# DPSD_NANO_2020-07-29_17-39-39.net
KiCad netlist of a schematic drawn in EasyEDA
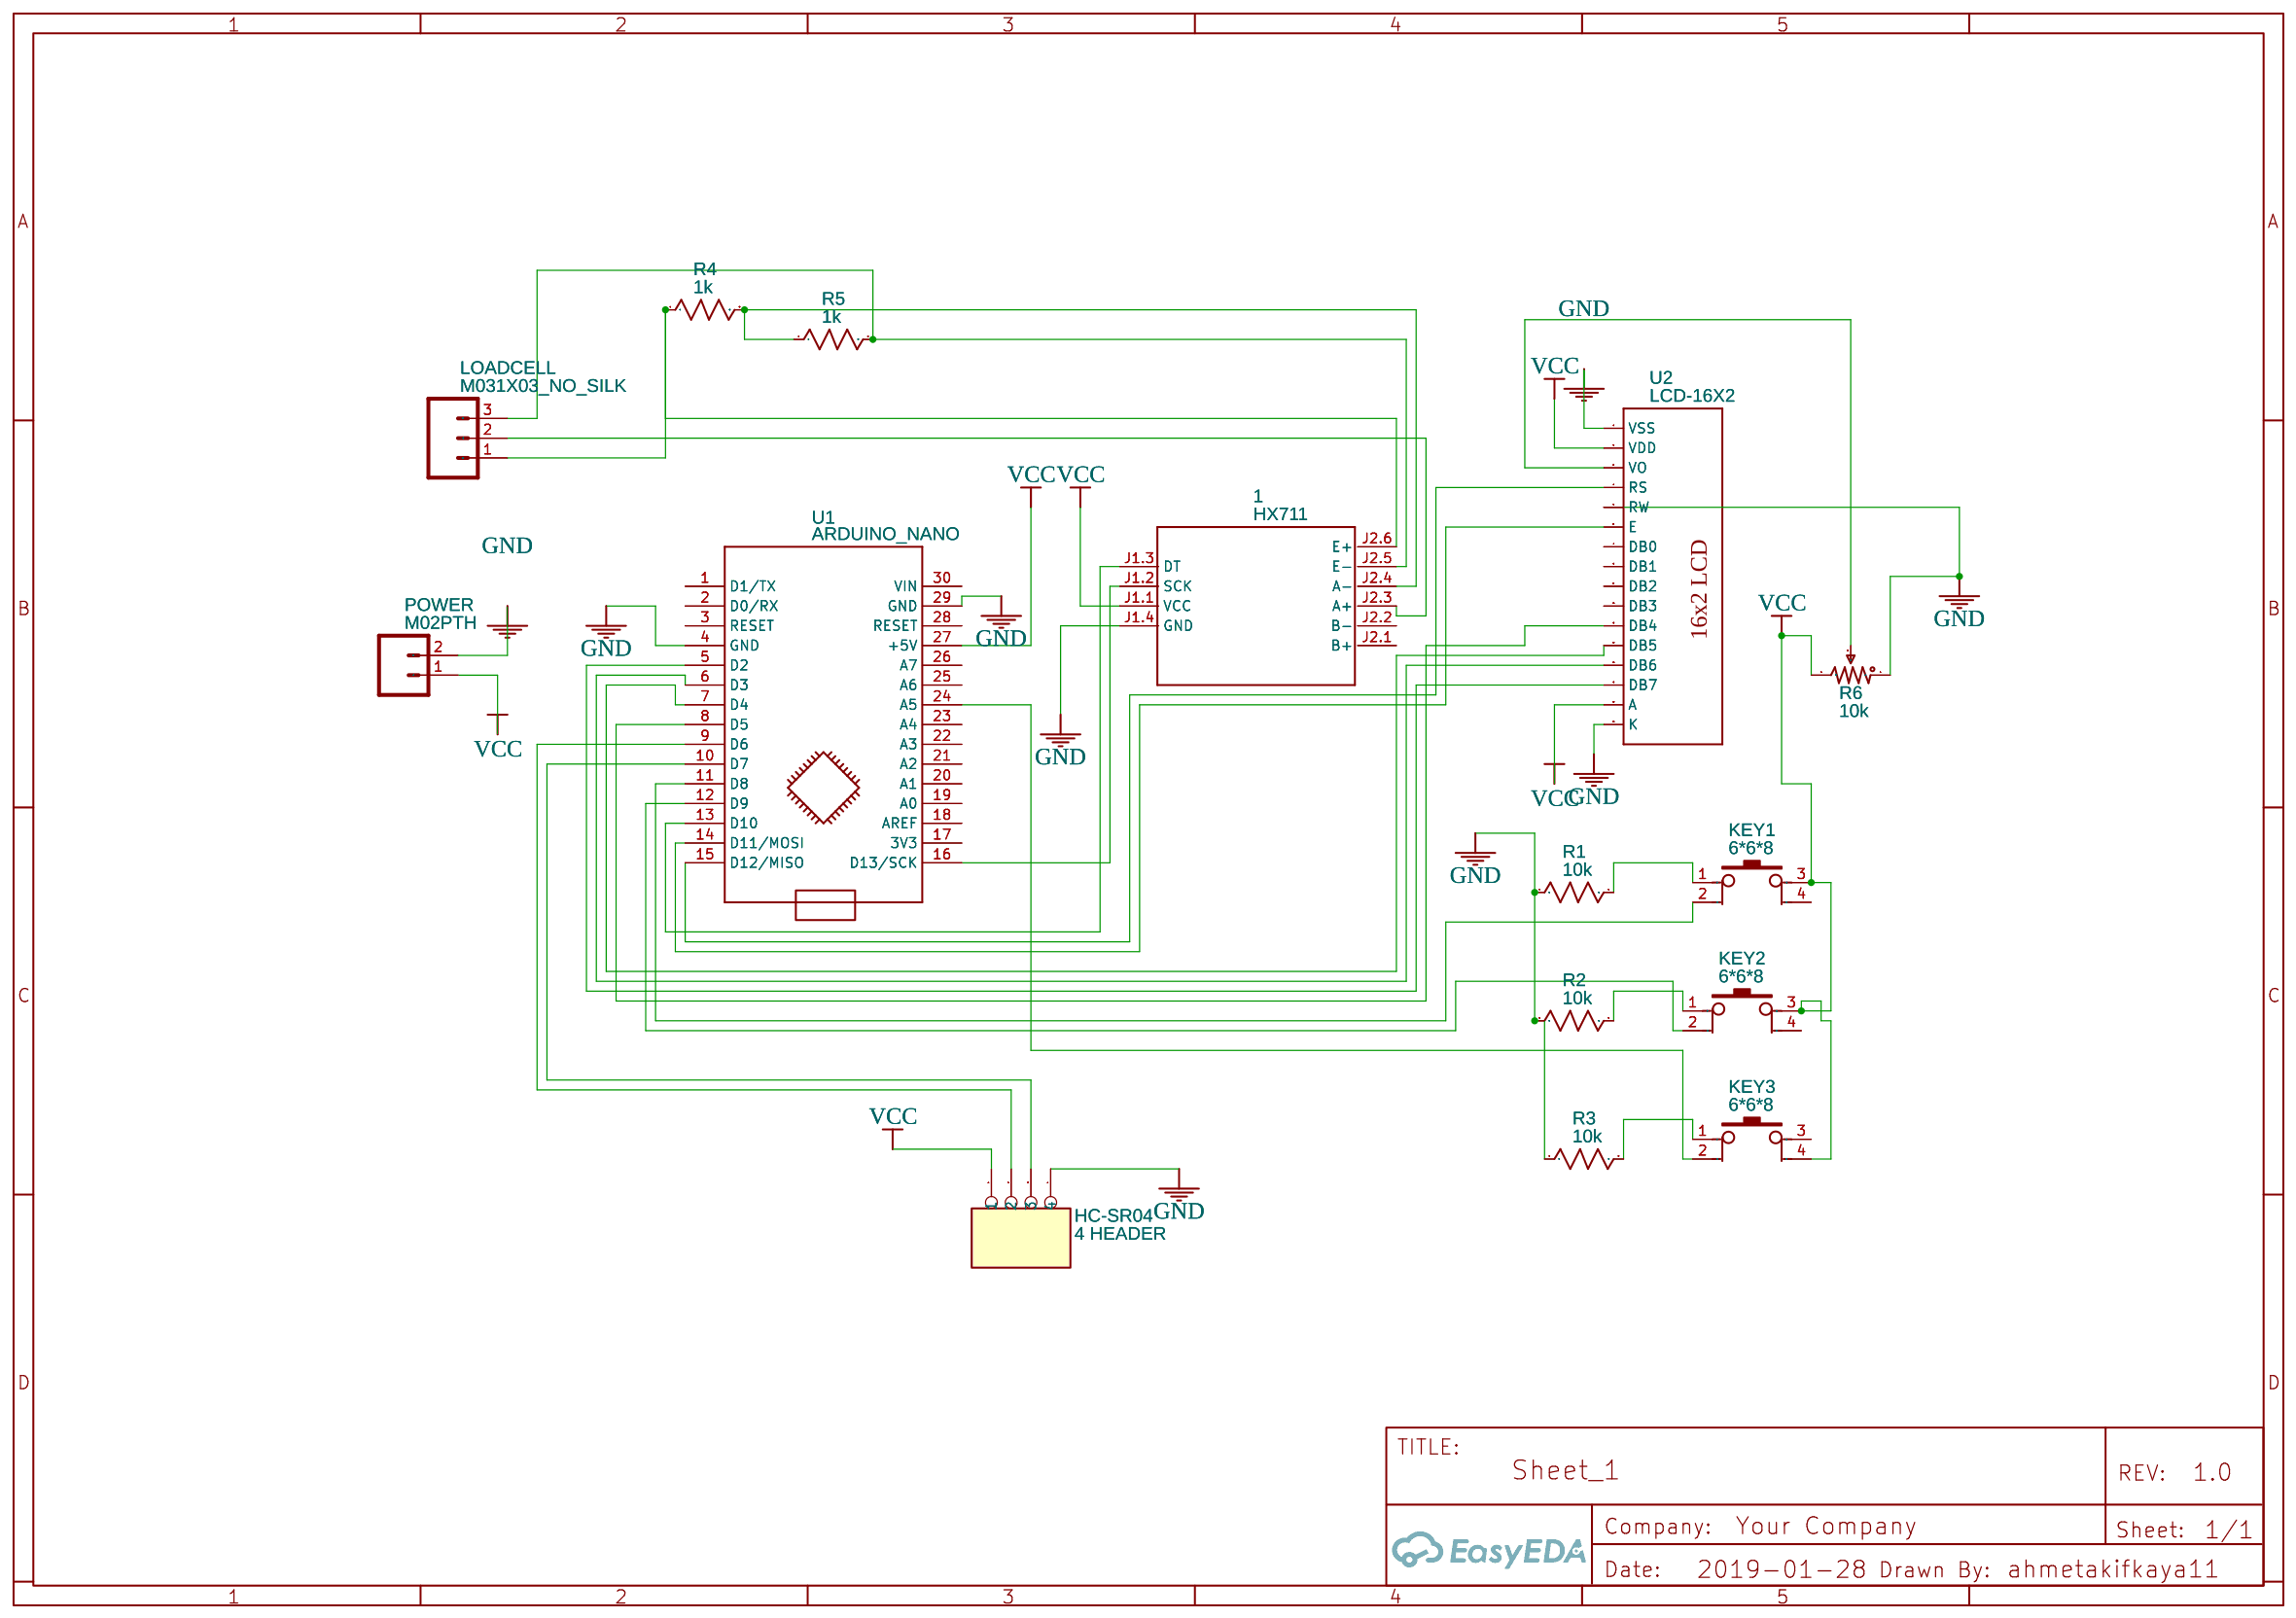
[diagram p0: schematic sheet]

(export (version "E")
  (design (tool "Eeschema 10.0.6"))
  (components
    (comp (ref "1")
      (value "HX711")
      (fields (field (name "BOM_Manufacturer Part") "?"))
      (libsource (lib "") (part "Unknown_630_300"))
    )
    (comp (ref "HC-SR04")
      (value "4 HEADER")
      (fields (field (name "BOM_Manufacturer Part") "?"))
      (libsource (lib "") (part "Unknown_510_610"))
    )
    (comp (ref "KEY1")
      (value "6*6*8")
      (fields
        (field (name "BOM_Manufacturer Part") "button6*6*8")
        (field (name "BOM_Supplier Part") "C59982")
      )
      (libsource (lib "") (part "Unknown_880_450"))
    )
    (comp (ref "KEY2")
      (value "6*6*8")
      (fields
        (field (name "BOM_Manufacturer Part") "button6*6*8")
        (field (name "BOM_Supplier Part") "C59982")
      )
      (libsource (lib "") (part "Unknown_875_515"))
    )
    (comp (ref "KEY3")
      (value "6*6*8")
      (fields
        (field (name "BOM_Manufacturer Part") "button6*6*8")
        (field (name "BOM_Supplier Part") "C59982")
      )
      (libsource (lib "") (part "Unknown_880_580"))
    )
    (comp (ref "LOADCELL")
      (value "M031X03_NO_SILK")
      (fields (field (name "BOM_Manufacturer Part") "?"))
      (libsource (lib "") (part "Unknown_220_215"))
    )
    (comp (ref "POWER")
      (value "M02PTH")
      (fields (field (name "BOM_Manufacturer Part") "?"))
      (libsource (lib "") (part "Unknown_195_335"))
    )
    (comp (ref "R1")
      (value "10k")
      (fields (field (name "BOM_Manufacturer Part") "?"))
      (libsource (lib "") (part "Res_AXIAL-0.3(1/8W)_US"))
    )
    (comp (ref "R2")
      (value "10k")
      (fields (field (name "BOM_Manufacturer Part") "?"))
      (libsource (lib "") (part "Res_AXIAL-0.3(1/8W)_US"))
    )
    (comp (ref "R3")
      (value "10k")
      (fields (field (name "BOM_Manufacturer Part") "?"))
      (libsource (lib "") (part "Res_AXIAL-0.3(1/8W)_US"))
    )
    (comp (ref "R4")
      (value "1k")
      (fields (field (name "BOM_Manufacturer Part") "?"))
      (libsource (lib "") (part "Res_AXIAL-0.3(1/8W)_US"))
    )
    (comp (ref "R5")
      (value "1k")
      (fields (field (name "BOM_Manufacturer Part") "?"))
      (libsource (lib "") (part "Res_AXIAL-0.3(1/8W)_US"))
    )
    (comp (ref "R6")
      (value "10k")
      (fields
        (field (name "BOM_Manufacturer Part") "3386P-1-101LF")
        (field (name "BOM_Supplier Part") "C125022")
      )
      (libsource (lib "") (part "3386P-1-101LF_US"))
    )
    (comp (ref "U1")
      (value "ARDUINO_NANO")
      (fields (field (name "BOM_Manufacturer Part") "?"))
      (libsource (lib "") (part "Unknown_410_365"))
    )
    (comp (ref "U2")
      (value "LCD-16X2")
      (fields (field (name "BOM_Manufacturer Part") "?"))
      (libsource (lib "") (part "Unknown_835_285"))
    )
  )
  (nets
    (net (code "1") (name "GND") (class "Default")
      (node (ref "1") (pin "J1.4") (pinfunction "GND_J1.4") (pintype "bidirectional"))
      (node (ref "HC-SR04") (pin "4") (pinfunction "4_4") (pintype "unspecified"))
      (node (ref "POWER") (pin "2") (pinfunction "2_2") (pintype "unspecified"))
      (node (ref "R1") (pin "1") (pinfunction "1_1") (pintype "unspecified"))
      (node (ref "R2") (pin "1") (pinfunction "1_1") (pintype "unspecified"))
      (node (ref "R3") (pin "1") (pinfunction "1_1") (pintype "unspecified"))
      (node (ref "R6") (pin "1") (pinfunction "1_1") (pintype "unspecified"))
      (node (ref "U1") (pin "29") (pinfunction "GND_29") (pintype "unspecified"))
      (node (ref "U1") (pin "4") (pinfunction "GND_4") (pintype "unspecified"))
      (node (ref "U2") (pin "1") (pinfunction "VSS_1") (pintype "passive"))
      (node (ref "U2") (pin "16") (pinfunction "K_16") (pintype "passive"))
      (node (ref "U2") (pin "5") (pinfunction "RW_5") (pintype "input"))
    )
    (net (code "2") (name "Net-(1-A+)") (class "Default")
      (node (ref "1") (pin "J2.3") (pinfunction "A+_J2.3") (pintype "bidirectional"))
      (node (ref "LOADCELL") (pin "2") (pinfunction "2_2") (pintype "unspecified"))
    )
    (net (code "3") (name "Net-(1-A-)") (class "Default")
      (node (ref "1") (pin "J2.4") (pinfunction "A-_J2.4") (pintype "bidirectional"))
      (node (ref "R4") (pin "2") (pinfunction "2_2") (pintype "unspecified"))
      (node (ref "R5") (pin "1") (pinfunction "1_1") (pintype "unspecified"))
    )
    (net (code "4") (name "Net-(1-DT)") (class "Default")
      (node (ref "1") (pin "J1.3") (pinfunction "DT_J1.3") (pintype "bidirectional"))
      (node (ref "U1") (pin "13") (pinfunction "D10_13") (pintype "unspecified"))
    )
    (net (code "5") (name "Net-(1-E+)") (class "Default")
      (node (ref "1") (pin "J2.6") (pinfunction "E+_J2.6") (pintype "bidirectional"))
      (node (ref "LOADCELL") (pin "1") (pinfunction "1_1") (pintype "unspecified"))
      (node (ref "R4") (pin "1") (pinfunction "1_1") (pintype "unspecified"))
    )
    (net (code "6") (name "Net-(1-E-)") (class "Default")
      (node (ref "1") (pin "J2.5") (pinfunction "E-_J2.5") (pintype "bidirectional"))
      (node (ref "LOADCELL") (pin "3") (pinfunction "3_3") (pintype "unspecified"))
      (node (ref "R5") (pin "2") (pinfunction "2_2") (pintype "unspecified"))
    )
    (net (code "7") (name "Net-(1-SCK)") (class "Default")
      (node (ref "1") (pin "J1.2") (pinfunction "SCK_J1.2") (pintype "bidirectional"))
      (node (ref "U1") (pin "16") (pinfunction "D13/SCK_16") (pintype "unspecified"))
    )
    (net (code "8") (name "Net-(KEY1-Pad1)") (class "Default")
      (node (ref "KEY1") (pin "1") (pinfunction "1_1") (pintype "input"))
      (node (ref "R1") (pin "2") (pinfunction "2_2") (pintype "unspecified"))
    )
    (net (code "9") (name "Net-(KEY2-Pad1)") (class "Default")
      (node (ref "KEY2") (pin "1") (pinfunction "1_1") (pintype "input"))
      (node (ref "R2") (pin "2") (pinfunction "2_2") (pintype "unspecified"))
    )
    (net (code "10") (name "Net-(KEY3-Pad1)") (class "Default")
      (node (ref "KEY3") (pin "1") (pinfunction "1_1") (pintype "input"))
      (node (ref "R3") (pin "2") (pinfunction "2_2") (pintype "unspecified"))
    )
    (net (code "11") (name "Net-(U1-A5)") (class "Default")
      (node (ref "KEY3") (pin "2") (pinfunction "2_2") (pintype "input"))
      (node (ref "U1") (pin "24") (pinfunction "A5_24") (pintype "unspecified"))
    )
    (net (code "12") (name "Net-(U1-D2)") (class "Default")
      (node (ref "U1") (pin "5") (pinfunction "D2_5") (pintype "unspecified"))
      (node (ref "U2") (pin "14") (pinfunction "DB7_14") (pintype "unspecified"))
    )
    (net (code "13") (name "Net-(U1-D3)") (class "Default")
      (node (ref "U1") (pin "6") (pinfunction "D3_6") (pintype "unspecified"))
      (node (ref "U2") (pin "13") (pinfunction "DB6_13") (pintype "unspecified"))
    )
    (net (code "14") (name "Net-(U1-D4)") (class "Default")
      (node (ref "U1") (pin "7") (pinfunction "D4_7") (pintype "unspecified"))
      (node (ref "U2") (pin "12") (pinfunction "DB5_12") (pintype "unspecified"))
    )
    (net (code "15") (name "Net-(U1-D5)") (class "Default")
      (node (ref "U1") (pin "8") (pinfunction "D5_8") (pintype "unspecified"))
      (node (ref "U2") (pin "11") (pinfunction "DB4_11") (pintype "unspecified"))
    )
    (net (code "16") (name "Net-(U1-D6)") (class "Default")
      (node (ref "HC-SR04") (pin "2") (pinfunction "2_2") (pintype "unspecified"))
      (node (ref "U1") (pin "9") (pinfunction "D6_9") (pintype "unspecified"))
    )
    (net (code "17") (name "Net-(U1-D7)") (class "Default")
      (node (ref "HC-SR04") (pin "3") (pinfunction "3_3") (pintype "unspecified"))
      (node (ref "U1") (pin "10") (pinfunction "D7_10") (pintype "unspecified"))
    )
    (net (code "18") (name "Net-(U1-D8)") (class "Default")
      (node (ref "KEY1") (pin "2") (pinfunction "2_2") (pintype "input"))
      (node (ref "U1") (pin "11") (pinfunction "D8_11") (pintype "unspecified"))
    )
    (net (code "19") (name "Net-(U1-D9)") (class "Default")
      (node (ref "KEY2") (pin "2") (pinfunction "2_2") (pintype "input"))
      (node (ref "U1") (pin "12") (pinfunction "D9_12") (pintype "unspecified"))
    )
    (net (code "20") (name "Net-(U1-D11{slash}MOSI)") (class "Default")
      (node (ref "U1") (pin "14") (pinfunction "D11/MOSI_14") (pintype "unspecified"))
      (node (ref "U2") (pin "6") (pinfunction "E_6") (pintype "input"))
    )
    (net (code "21") (name "Net-(U1-D12{slash}MISO)") (class "Default")
      (node (ref "U1") (pin "15") (pinfunction "D12/MISO_15") (pintype "unspecified"))
      (node (ref "U2") (pin "4") (pinfunction "RS_4") (pintype "input"))
    )
    (net (code "22") (name "Net-(U2-VO)") (class "Default")
      (node (ref "R6") (pin "2") (pinfunction "2_2") (pintype "unspecified"))
      (node (ref "U2") (pin "3") (pinfunction "VO_3") (pintype "unspecified"))
    )
    (net (code "23") (name "VCC") (class "Default")
      (node (ref "1") (pin "J1.1") (pinfunction "VCC_J1.1") (pintype "bidirectional"))
      (node (ref "HC-SR04") (pin "1") (pinfunction "1_1") (pintype "unspecified"))
      (node (ref "KEY1") (pin "3") (pinfunction "3_3") (pintype "input"))
      (node (ref "KEY2") (pin "3") (pinfunction "3_3") (pintype "input"))
      (node (ref "KEY3") (pin "4") (pinfunction "4_4") (pintype "input"))
      (node (ref "POWER") (pin "1") (pinfunction "1_1") (pintype "unspecified"))
      (node (ref "R6") (pin "3") (pinfunction "3_3") (pintype "unspecified"))
      (node (ref "U1") (pin "27") (pinfunction "+5V_27") (pintype "unspecified"))
      (node (ref "U2") (pin "15") (pinfunction "A_15") (pintype "passive"))
      (node (ref "U2") (pin "2") (pinfunction "VDD_2") (pintype "passive"))
    )
    (net (code "24") (name "unconnected-(1-B+-PadJ2.1)") (class "Default")
      (node (ref "1") (pin "J2.1") (pinfunction "B+_J2.1") (pintype "bidirectional"))
    )
    (net (code "25") (name "unconnected-(1-B--PadJ2.2)") (class "Default")
      (node (ref "1") (pin "J2.2") (pinfunction "B-_J2.2") (pintype "bidirectional"))
    )
    (net (code "26") (name "unconnected-(KEY1-Pad4)") (class "Default")
      (node (ref "KEY1") (pin "4") (pinfunction "4_4") (pintype "input"))
    )
    (net (code "27") (name "unconnected-(KEY2-Pad4)") (class "Default")
      (node (ref "KEY2") (pin "4") (pinfunction "4_4") (pintype "input"))
    )
    (net (code "28") (name "unconnected-(KEY3-Pad3)") (class "Default")
      (node (ref "KEY3") (pin "3") (pinfunction "3_3") (pintype "input"))
    )
    (net (code "29") (name "unconnected-(U1-3V3-Pad17)") (class "Default")
      (node (ref "U1") (pin "17") (pinfunction "3V3_17") (pintype "unspecified"))
    )
    (net (code "30") (name "unconnected-(U1-A0-Pad19)") (class "Default")
      (node (ref "U1") (pin "19") (pinfunction "A0_19") (pintype "unspecified"))
    )
    (net (code "31") (name "unconnected-(U1-A1-Pad20)") (class "Default")
      (node (ref "U1") (pin "20") (pinfunction "A1_20") (pintype "unspecified"))
    )
    (net (code "32") (name "unconnected-(U1-A2-Pad21)") (class "Default")
      (node (ref "U1") (pin "21") (pinfunction "A2_21") (pintype "unspecified"))
    )
    (net (code "33") (name "unconnected-(U1-A3-Pad22)") (class "Default")
      (node (ref "U1") (pin "22") (pinfunction "A3_22") (pintype "unspecified"))
    )
    (net (code "34") (name "unconnected-(U1-A4-Pad23)") (class "Default")
      (node (ref "U1") (pin "23") (pinfunction "A4_23") (pintype "unspecified"))
    )
    (net (code "35") (name "unconnected-(U1-A6-Pad25)") (class "Default")
      (node (ref "U1") (pin "25") (pinfunction "A6_25") (pintype "unspecified"))
    )
    (net (code "36") (name "unconnected-(U1-A7-Pad26)") (class "Default")
      (node (ref "U1") (pin "26") (pinfunction "A7_26") (pintype "unspecified"))
    )
    (net (code "37") (name "unconnected-(U1-AREF-Pad18)") (class "Default")
      (node (ref "U1") (pin "18") (pinfunction "AREF_18") (pintype "unspecified"))
    )
    (net (code "38") (name "unconnected-(U1-D0{slash}RX-Pad2)") (class "Default")
      (node (ref "U1") (pin "2") (pinfunction "D0/RX_2") (pintype "unspecified"))
    )
    (net (code "39") (name "unconnected-(U1-D1{slash}TX-Pad1)") (class "Default")
      (node (ref "U1") (pin "1") (pinfunction "D1/TX_1") (pintype "unspecified"))
    )
    (net (code "40") (name "unconnected-(U1-RESET-Pad3)") (class "Default")
      (node (ref "U1") (pin "3") (pinfunction "RESET_3") (pintype "unspecified"))
    )
    (net (code "41") (name "unconnected-(U1-RESET-Pad28)") (class "Default")
      (node (ref "U1") (pin "28") (pinfunction "RESET_28") (pintype "unspecified"))
    )
    (net (code "42") (name "unconnected-(U1-VIN-Pad30)") (class "Default")
      (node (ref "U1") (pin "30") (pinfunction "VIN_30") (pintype "unspecified"))
    )
    (net (code "43") (name "unconnected-(U2-DB0-Pad7)") (class "Default")
      (node (ref "U2") (pin "7") (pinfunction "DB0_7") (pintype "unspecified"))
    )
    (net (code "44") (name "unconnected-(U2-DB1-Pad8)") (class "Default")
      (node (ref "U2") (pin "8") (pinfunction "DB1_8") (pintype "unspecified"))
    )
    (net (code "45") (name "unconnected-(U2-DB2-Pad9)") (class "Default")
      (node (ref "U2") (pin "9") (pinfunction "DB2_9") (pintype "unspecified"))
    )
    (net (code "46") (name "unconnected-(U2-DB3-Pad10)") (class "Default")
      (node (ref "U2") (pin "10") (pinfunction "DB3_10") (pintype "unspecified"))
    )
  )
)
